# CircleValve.net
KiCad netlist of a schematic drawn in Altium Designer
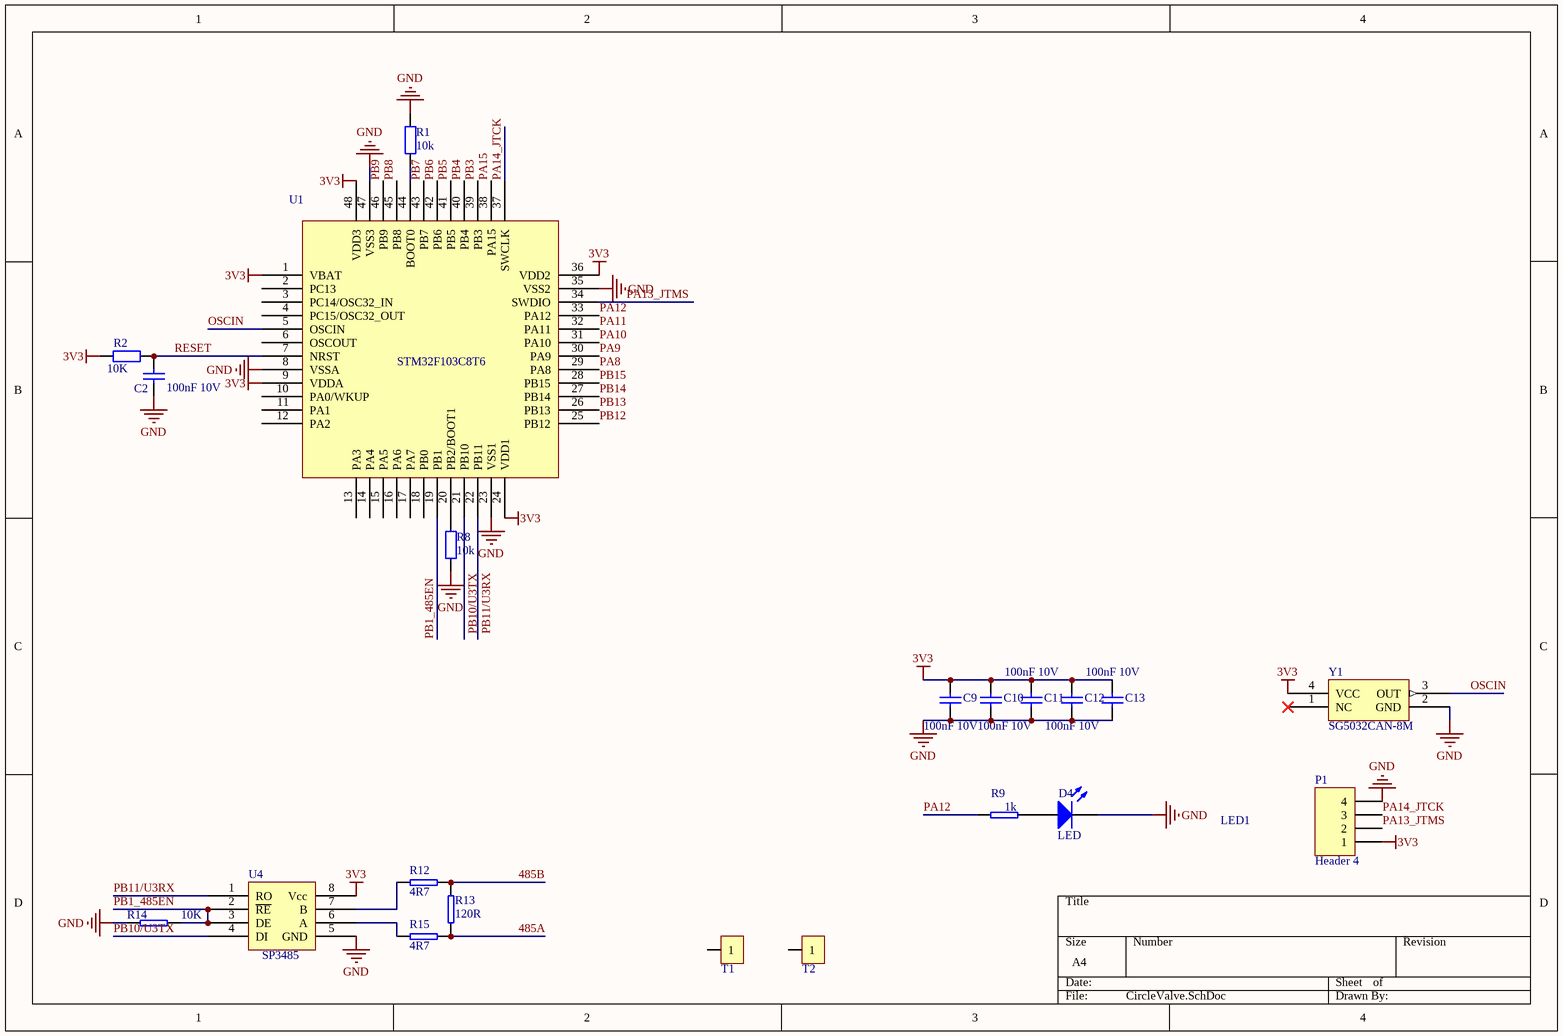
[diagram p0: CircleValve.SchDoc]

(export (version "E")
  (design (tool "Eeschema 10.0.6"))
  (components
    (comp (ref "C2") (value "100nF 10V") (footprint "C0603") (libsource (lib "stm32_s") (part "CAP")))
    (comp (ref "C9") (value "100nF 10V") (footprint "C0603") (libsource (lib "stm32_s") (part "CAP")))
    (comp (ref "C10") (value "100nF 10V") (footprint "C0603") (libsource (lib "stm32_s") (part "CAP")))
    (comp (ref "C11") (value "100nF 10V") (footprint "C0603") (libsource (lib "stm32_s") (part "CAP")))
    (comp (ref "C12") (value "100nF 10V") (footprint "C0603") (libsource (lib "stm32_s") (part "CAP")))
    (comp (ref "C13") (value "100nF 10V") (footprint "C0603") (libsource (lib "stm32_s") (part "CAP")))
    (comp (ref "D4")
      (value "LED")
      (footprint "LED_M")
      (description "绿色")
      (libsource (lib "stm32_s") (part "LED"))
    )
    (comp (ref "P1")
      (value "Header 4")
      (footprint "Header4-2.54mm")
      (description "Header, 4-Pin")
      (fields (field (name "PUBLISHER") "Altium Limited"))
      (libsource (lib "Miscellaneous Connectors") (part "Header 4"))
    )
    (comp (ref "R1") (value "10k") (footprint "R0603") (libsource (lib "stm32") (part "RES")))
    (comp (ref "R2") (value "10K") (footprint "R0603") (libsource (lib "stm32_s") (part "RES")))
    (comp (ref "R8") (value "10k") (footprint "R0603") (libsource (lib "stm32") (part "RES")))
    (comp (ref "R9")
      (value "1k")
      (footprint "R0603")
      (description "标贴电阻")
      (libsource (lib "stm32_s") (part "R"))
    )
    (comp (ref "R12")
      (value "4R7")
      (footprint "R0603")
      (description "标贴电阻")
      (libsource (lib "stm32_s") (part "R"))
    )
    (comp (ref "R13")
      (value "120R")
      (footprint "R0603")
      (description "标贴电阻")
      (libsource (lib "stm32_s") (part "R"))
    )
    (comp (ref "R14")
      (value "10K")
      (footprint "R0603")
      (description "标贴电阻")
      (libsource (lib "stm32_s") (part "R"))
    )
    (comp (ref "R15")
      (value "4R7")
      (footprint "R0603")
      (description "标贴电阻")
      (libsource (lib "stm32_s") (part "R"))
    )
    (comp (ref "T1") (value "TP") (footprint "定位孔3mm") (libsource (lib "stm32_s") (part "TP")))
    (comp (ref "T2") (value "TP") (footprint "定位孔3mm") (libsource (lib "stm32_s") (part "TP")))
    (comp (ref "U1")
      (value "STM32F103C8T6")
      (footprint "LQFP-48_7x7x05P")
      (libsource (lib "库") (part "STM32F103C8T6"))
    )
    (comp (ref "U4") (value "SP3485") (footprint "SO8") (libsource (lib "stm32_s") (part "RS485")))
    (comp (ref "Y1")
      (value "SG5032CAN-8M")
      (footprint "XTAL-4P-5*3MM")
      (description "贴片有源晶振-8M")
      (libsource (lib "Freq") (part "XTAL_POWER"))
    )
  )
  (nets
    (net (code "1") (name "/485A") (class "Default")
      (node (ref "R13") (pin "2") (pinfunction "2_2") (pintype "passive"))
      (node (ref "R15") (pin "1") (pinfunction "1_1") (pintype "passive"))
    )
    (net (code "2") (name "/485B") (class "Default")
      (node (ref "R12") (pin "1") (pinfunction "1_1") (pintype "passive"))
      (node (ref "R13") (pin "1") (pinfunction "1_1") (pintype "passive"))
    )
    (net (code "3") (name "/OSCIN") (class "Default")
      (node (ref "U1") (pin "5") (pinfunction "OSCIN_5") (pintype "passive"))
      (node (ref "Y1") (pin "3") (pinfunction "OUT_3") (pintype "output"))
    )
    (net (code "4") (name "/PA8") (class "Default")
      (node (ref "U1") (pin "29") (pinfunction "PA8_29") (pintype "passive"))
    )
    (net (code "5") (name "/PA9") (class "Default")
      (node (ref "U1") (pin "30") (pinfunction "PA9_30") (pintype "passive"))
    )
    (net (code "6") (name "/PA10") (class "Default")
      (node (ref "U1") (pin "31") (pinfunction "PA10_31") (pintype "passive"))
    )
    (net (code "7") (name "/PA11") (class "Default")
      (node (ref "U1") (pin "32") (pinfunction "PA11_32") (pintype "passive"))
    )
    (net (code "8") (name "/PA12") (class "Default")
      (node (ref "R9") (pin "1") (pinfunction "1_1") (pintype "passive"))
      (node (ref "U1") (pin "33") (pinfunction "PA12_33") (pintype "passive"))
    )
    (net (code "9") (name "/PA13_JTMS") (class "Default")
      (node (ref "P1") (pin "2") (pinfunction "2_2") (pintype "passive"))
      (node (ref "U1") (pin "34") (pinfunction "SWDIO_34") (pintype "passive"))
    )
    (net (code "10") (name "/PA14_JTCK") (class "Default")
      (node (ref "P1") (pin "3") (pinfunction "3_3") (pintype "passive"))
      (node (ref "U1") (pin "37") (pinfunction "SWCLK_37") (pintype "passive"))
    )
    (net (code "11") (name "/PA15") (class "Default")
      (node (ref "U1") (pin "38") (pinfunction "PA15_38") (pintype "passive"))
    )
    (net (code "12") (name "/PB1_485EN") (class "Default")
      (node (ref "R14") (pin "2") (pinfunction "2_2") (pintype "passive"))
      (node (ref "U1") (pin "19") (pinfunction "PB1_19") (pintype "passive"))
      (node (ref "U4") (pin "2") (pinfunction "~{RE}_2") (pintype "passive"))
      (node (ref "U4") (pin "3") (pinfunction "DE_3") (pintype "passive"))
    )
    (net (code "13") (name "/PB3") (class "Default")
      (node (ref "U1") (pin "39") (pinfunction "PB3_39") (pintype "passive"))
    )
    (net (code "14") (name "/PB4") (class "Default")
      (node (ref "U1") (pin "40") (pinfunction "PB4_40") (pintype "passive"))
    )
    (net (code "15") (name "/PB5") (class "Default")
      (node (ref "U1") (pin "41") (pinfunction "PB5_41") (pintype "passive"))
    )
    (net (code "16") (name "/PB6") (class "Default")
      (node (ref "U1") (pin "42") (pinfunction "PB6_42") (pintype "passive"))
    )
    (net (code "17") (name "/PB7") (class "Default")
      (node (ref "U1") (pin "43") (pinfunction "PB7_43") (pintype "passive"))
    )
    (net (code "18") (name "/PB8") (class "Default")
      (node (ref "U1") (pin "45") (pinfunction "PB8_45") (pintype "passive"))
    )
    (net (code "19") (name "/PB9") (class "Default")
      (node (ref "U1") (pin "46") (pinfunction "PB9_46") (pintype "passive"))
    )
    (net (code "20") (name "/PB10{slash}U3TX") (class "Default")
      (node (ref "U1") (pin "21") (pinfunction "PB10_21") (pintype "passive"))
      (node (ref "U4") (pin "4") (pinfunction "DI_4") (pintype "passive"))
    )
    (net (code "21") (name "/PB11{slash}U3RX") (class "Default")
      (node (ref "U1") (pin "22") (pinfunction "PB11_22") (pintype "passive"))
      (node (ref "U4") (pin "1") (pinfunction "RO_1") (pintype "passive"))
    )
    (net (code "22") (name "/PB12") (class "Default")
      (node (ref "U1") (pin "25") (pinfunction "PB12_25") (pintype "passive"))
    )
    (net (code "23") (name "/PB13") (class "Default")
      (node (ref "U1") (pin "26") (pinfunction "PB13_26") (pintype "passive"))
    )
    (net (code "24") (name "/PB14") (class "Default")
      (node (ref "U1") (pin "27") (pinfunction "PB14_27") (pintype "passive"))
    )
    (net (code "25") (name "/PB15") (class "Default")
      (node (ref "U1") (pin "28") (pinfunction "PB15_28") (pintype "passive"))
    )
    (net (code "26") (name "/RESET") (class "Default")
      (node (ref "C2") (pin "1") (pinfunction "1_1") (pintype "passive"))
      (node (ref "R2") (pin "2") (pinfunction "2_2") (pintype "passive"))
      (node (ref "U1") (pin "7") (pinfunction "NRST_7") (pintype "passive"))
    )
    (net (code "27") (name "3V3") (class "Default")
      (node (ref "C10") (pin "2") (pinfunction "2_2") (pintype "passive"))
      (node (ref "C11") (pin "2") (pinfunction "2_2") (pintype "passive"))
      (node (ref "C12") (pin "2") (pinfunction "2_2") (pintype "passive"))
      (node (ref "C13") (pin "2") (pinfunction "2_2") (pintype "passive"))
      (node (ref "C9") (pin "2") (pinfunction "2_2") (pintype "passive"))
      (node (ref "P1") (pin "1") (pinfunction "1_1") (pintype "passive"))
      (node (ref "R2") (pin "1") (pinfunction "1_1") (pintype "passive"))
      (node (ref "U1") (pin "1") (pinfunction "VBAT_1") (pintype "passive"))
      (node (ref "U1") (pin "24") (pinfunction "VDD1_24") (pintype "passive"))
      (node (ref "U1") (pin "36") (pinfunction "VDD2_36") (pintype "passive"))
      (node (ref "U1") (pin "48") (pinfunction "VDD3_48") (pintype "passive"))
      (node (ref "U1") (pin "9") (pinfunction "VDDA_9") (pintype "passive"))
      (node (ref "U4") (pin "8") (pinfunction "Vcc_8") (pintype "passive"))
      (node (ref "Y1") (pin "4") (pinfunction "VCC_4") (pintype "passive"))
    )
    (net (code "28") (name "GND") (class "Default")
      (node (ref "C10") (pin "1") (pinfunction "1_1") (pintype "passive"))
      (node (ref "C11") (pin "1") (pinfunction "1_1") (pintype "passive"))
      (node (ref "C12") (pin "1") (pinfunction "1_1") (pintype "passive"))
      (node (ref "C13") (pin "1") (pinfunction "1_1") (pintype "passive"))
      (node (ref "C2") (pin "2") (pinfunction "2_2") (pintype "passive"))
      (node (ref "C9") (pin "1") (pinfunction "1_1") (pintype "passive"))
      (node (ref "D4") (pin "2") (pinfunction "K_2") (pintype "passive"))
      (node (ref "P1") (pin "4") (pinfunction "4_4") (pintype "passive"))
      (node (ref "R1") (pin "2") (pinfunction "2_2") (pintype "passive"))
      (node (ref "R14") (pin "1") (pinfunction "1_1") (pintype "passive"))
      (node (ref "R8") (pin "1") (pinfunction "1_1") (pintype "passive"))
      (node (ref "U1") (pin "23") (pinfunction "VSS1_23") (pintype "passive"))
      (node (ref "U1") (pin "35") (pinfunction "VSS2_35") (pintype "passive"))
      (node (ref "U1") (pin "47") (pinfunction "VSS3_47") (pintype "passive"))
      (node (ref "U1") (pin "8") (pinfunction "VSSA_8") (pintype "passive"))
      (node (ref "U4") (pin "5") (pinfunction "GND_5") (pintype "passive"))
      (node (ref "Y1") (pin "2") (pinfunction "GND_2") (pintype "passive"))
    )
    (net (code "29") (name "Net-(D4-A)") (class "Default")
      (node (ref "D4") (pin "1") (pinfunction "A_1") (pintype "passive"))
      (node (ref "R9") (pin "2") (pinfunction "2_2") (pintype "passive"))
    )
    (net (code "30") (name "Net-(U1-BOOT0)") (class "Default")
      (node (ref "R1") (pin "1") (pinfunction "1_1") (pintype "passive"))
      (node (ref "U1") (pin "44") (pinfunction "BOOT0_44") (pintype "passive"))
    )
    (net (code "31") (name "Net-(U1-PB2{slash}BOOT1)") (class "Default")
      (node (ref "R8") (pin "2") (pinfunction "2_2") (pintype "passive"))
      (node (ref "U1") (pin "20") (pinfunction "PB2/BOOT1_20") (pintype "passive"))
    )
    (net (code "32") (name "Net-(U4-A)") (class "Default")
      (node (ref "R15") (pin "2") (pinfunction "2_2") (pintype "passive"))
      (node (ref "U4") (pin "6") (pinfunction "A_6") (pintype "passive"))
    )
    (net (code "33") (name "Net-(U4-B)") (class "Default")
      (node (ref "R12") (pin "2") (pinfunction "2_2") (pintype "passive"))
      (node (ref "U4") (pin "7") (pinfunction "B_7") (pintype "passive"))
    )
    (net (code "34") (name "unconnected-(T1-Pad1)") (class "Default")
      (node (ref "T1") (pin "1") (pinfunction "1_1") (pintype "passive"))
    )
    (net (code "35") (name "unconnected-(T2-Pad1)") (class "Default")
      (node (ref "T2") (pin "1") (pinfunction "1_1") (pintype "passive"))
    )
    (net (code "36") (name "unconnected-(U1-OSCOUT-Pad6)") (class "Default")
      (node (ref "U1") (pin "6") (pinfunction "OSCOUT_6") (pintype "passive"))
    )
    (net (code "37") (name "unconnected-(U1-PA0{slash}WKUP-Pad10)") (class "Default")
      (node (ref "U1") (pin "10") (pinfunction "PA0/WKUP_10") (pintype "passive"))
    )
    (net (code "38") (name "unconnected-(U1-PA1-Pad11)") (class "Default")
      (node (ref "U1") (pin "11") (pinfunction "PA1_11") (pintype "passive"))
    )
    (net (code "39") (name "unconnected-(U1-PA2-Pad12)") (class "Default")
      (node (ref "U1") (pin "12") (pinfunction "PA2_12") (pintype "passive"))
    )
    (net (code "40") (name "unconnected-(U1-PA3-Pad13)") (class "Default")
      (node (ref "U1") (pin "13") (pinfunction "PA3_13") (pintype "passive"))
    )
    (net (code "41") (name "unconnected-(U1-PA4-Pad14)") (class "Default")
      (node (ref "U1") (pin "14") (pinfunction "PA4_14") (pintype "passive"))
    )
    (net (code "42") (name "unconnected-(U1-PA5-Pad15)") (class "Default")
      (node (ref "U1") (pin "15") (pinfunction "PA5_15") (pintype "passive"))
    )
    (net (code "43") (name "unconnected-(U1-PA6-Pad16)") (class "Default")
      (node (ref "U1") (pin "16") (pinfunction "PA6_16") (pintype "passive"))
    )
    (net (code "44") (name "unconnected-(U1-PA7-Pad17)") (class "Default")
      (node (ref "U1") (pin "17") (pinfunction "PA7_17") (pintype "passive"))
    )
    (net (code "45") (name "unconnected-(U1-PB0-Pad18)") (class "Default")
      (node (ref "U1") (pin "18") (pinfunction "PB0_18") (pintype "passive"))
    )
    (net (code "46") (name "unconnected-(U1-PC13-Pad2)") (class "Default")
      (node (ref "U1") (pin "2") (pinfunction "PC13_2") (pintype "passive"))
    )
    (net (code "47") (name "unconnected-(U1-PC14{slash}OSC32_IN-Pad3)") (class "Default")
      (node (ref "U1") (pin "3") (pinfunction "PC14/OSC32_IN_3") (pintype "passive"))
    )
    (net (code "48") (name "unconnected-(U1-PC15{slash}OSC32_OUT-Pad4)") (class "Default")
      (node (ref "U1") (pin "4") (pinfunction "PC15/OSC32_OUT_4") (pintype "passive"))
    )
    (net (code "49") (name "unconnected-(Y1-NC-Pad1)") (class "Default")
      (node (ref "Y1") (pin "1") (pinfunction "NC_1") (pintype "passive+no_connect"))
    )
  )
)
